# buckler.net
KiCad netlist of a schematic drawn in EAGLE
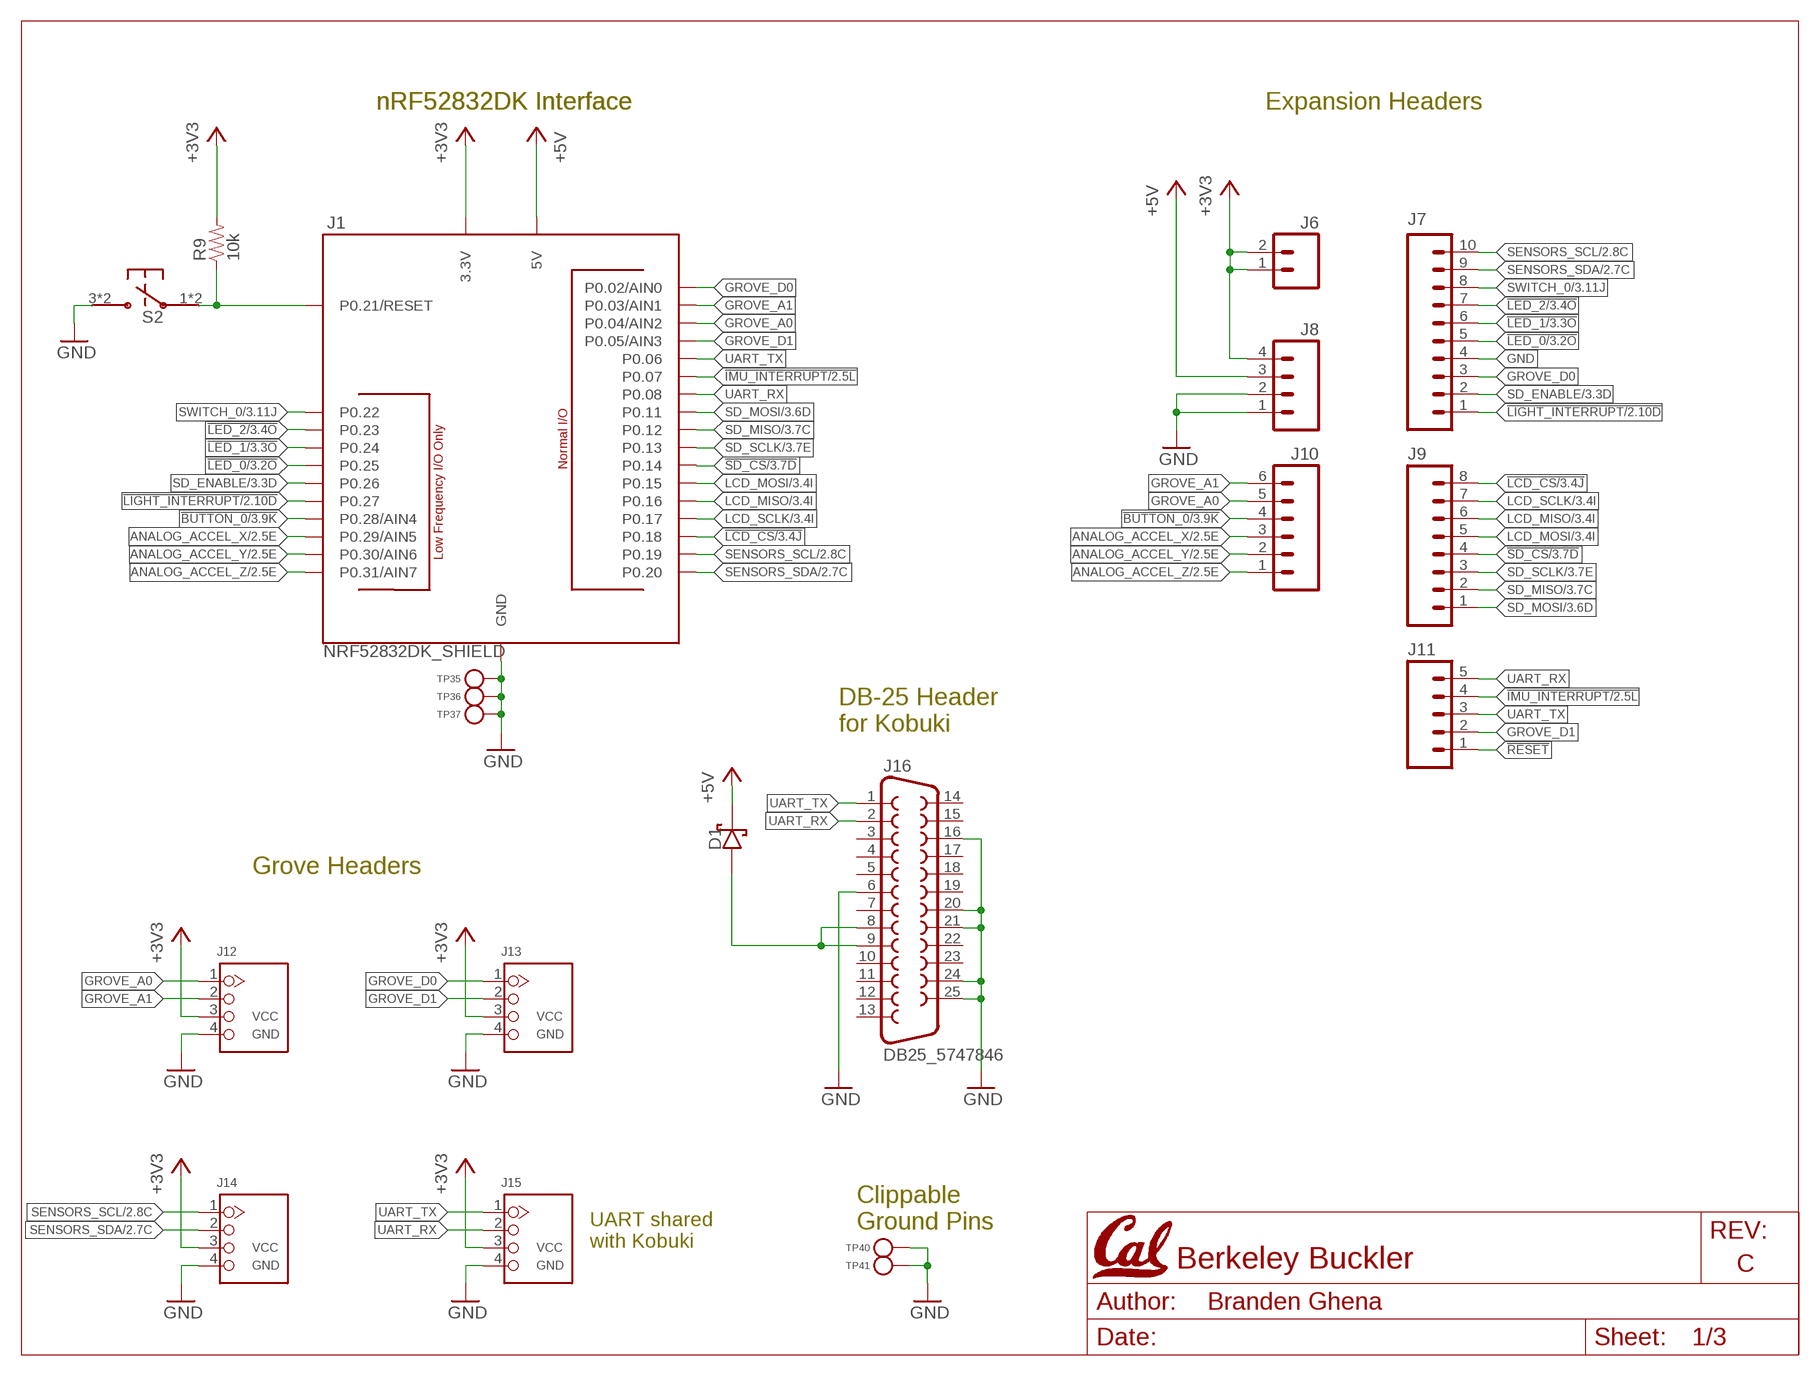
[diagram p0: schematic, sheet 1]
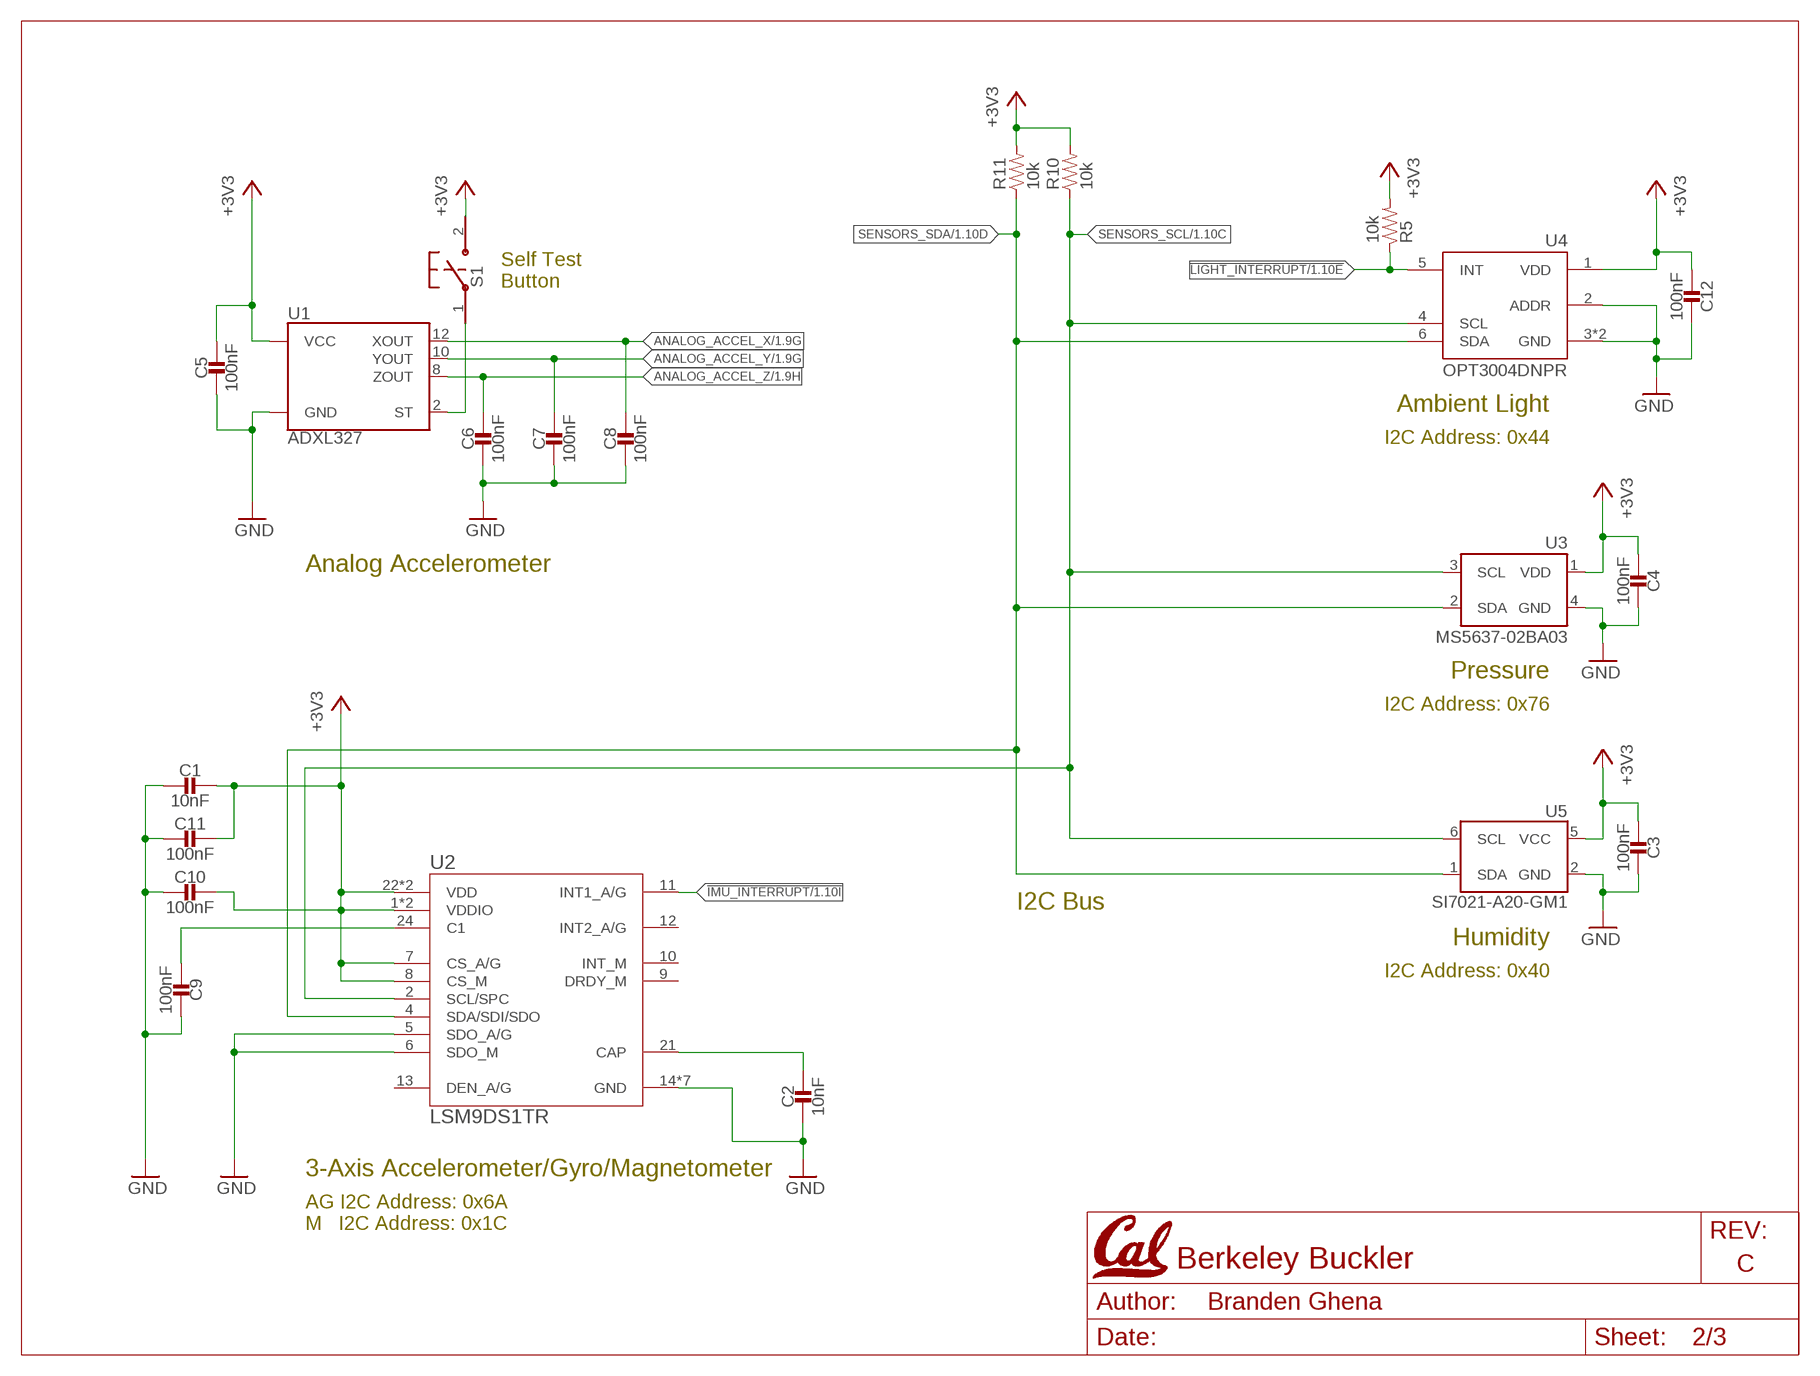
[diagram p1: schematic, sheet 2]
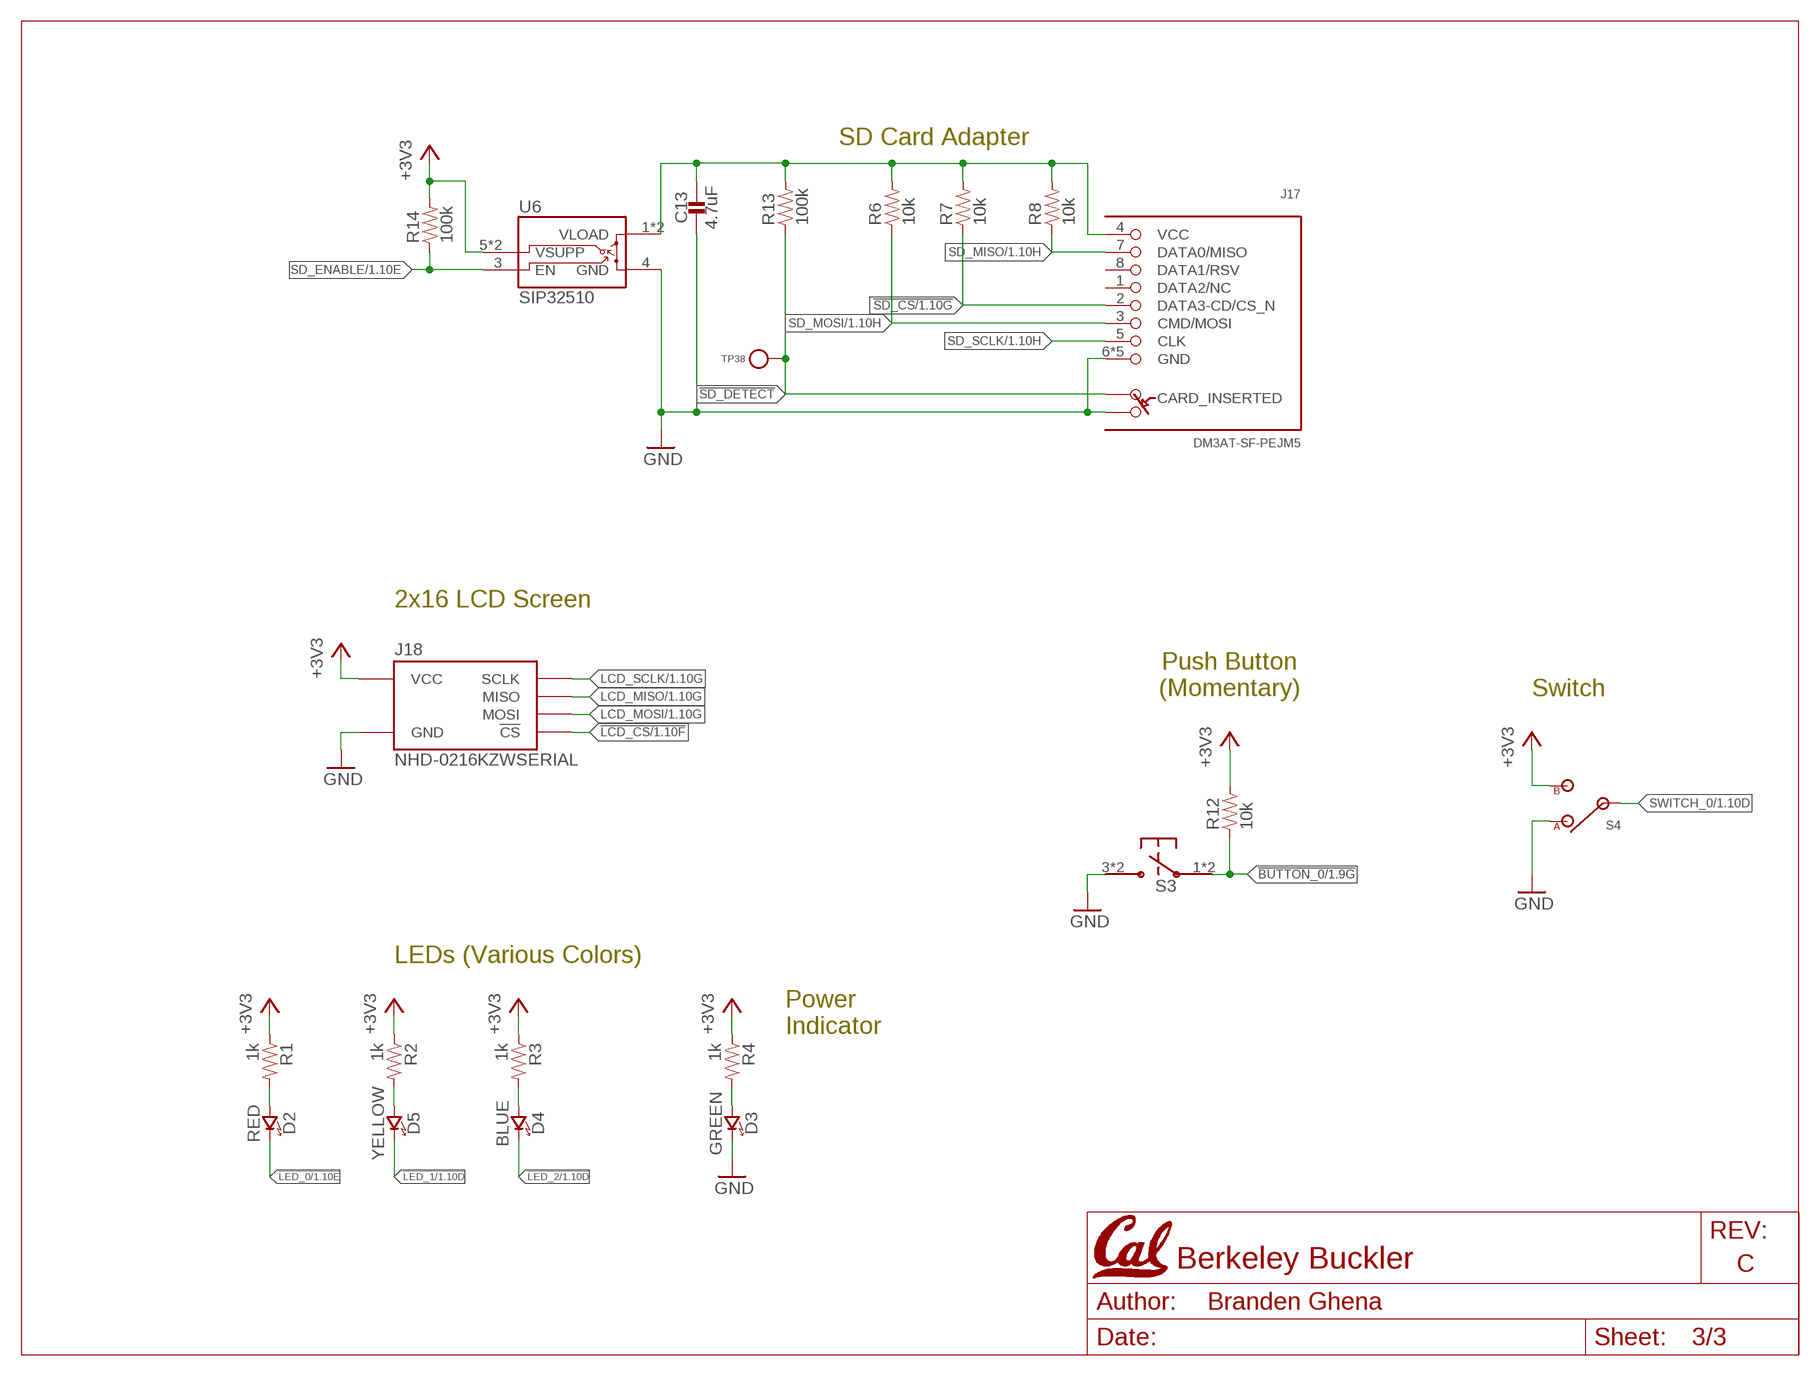
[diagram p2: schematic, sheet 3]

(export (version "E")
  (design (tool "Eeschema 10.0.6"))
  (components
    (comp (ref "D1")
      (value "DIODE_SCHOTTKYSOD323")
      (footprint "eagle-import:SOD323")
      (description "DIODE SCHOTTKY 30V 500MA SOD323")
      (fields (field (name "MANUFACTURER") "Diodes Incorporated") (field (name "MPN") "B0530WS-7-F"))
      (libsource (lib "eagle-import") (part "DIODE_SCHOTTKYSOD323"))
    )
    (comp (ref "J1")
      (value "NRF52832DK_SHIELD")
      (footprint "eagle-import:NRF52832DK_SHIELD")
      (libsource (lib "eagle-import") (part "NRF52832DK_SHIELD"))
    )
    (comp (ref "J6")
      (value "M02PTH")
      (footprint "eagle-import:1X02")
      (libsource (lib "eagle-import") (part "M02PTH"))
    )
    (comp (ref "J7")
      (value "M10\"")
      (footprint "eagle-import:1X10")
      (libsource (lib "eagle-import") (part "M10{dblquote}"))
    )
    (comp (ref "J8")
      (value "M04PTH")
      (footprint "eagle-import:1X04")
      (libsource (lib "eagle-import") (part "M04PTH"))
    )
    (comp (ref "J9")
      (value "M081X08")
      (footprint "eagle-import:1X08")
      (libsource (lib "eagle-import") (part "M081X08"))
    )
    (comp (ref "J10")
      (value "M06SIP")
      (footprint "eagle-import:1X06")
      (libsource (lib "eagle-import") (part "M06SIP"))
    )
    (comp (ref "J11")
      (value "M05PTH")
      (footprint "eagle-import:1X05")
      (libsource (lib "eagle-import") (part "M05PTH"))
    )
    (comp (ref "J12")
      (value "GROVE-CONNECTOR-DIP(4P-2.0)")
      (footprint "eagle-import:HW4-2.0")
      (description "Grove - Universal 4 pin connector")
      (fields (field (name "MANUFACTURER") "Seeed Studio") (field (name "MPN") "110990030"))
      (libsource (lib "eagle-import") (part "GROVE-CONNECTOR-DIP(4P-2.0)"))
    )
    (comp (ref "J13")
      (value "GROVE-CONNECTOR-DIP(4P-2.0)")
      (footprint "eagle-import:HW4-2.0")
      (description "Grove - Universal 4 pin connector")
      (fields (field (name "MANUFACTURER") "Seeed Studio") (field (name "MPN") "110990030"))
      (libsource (lib "eagle-import") (part "GROVE-CONNECTOR-DIP(4P-2.0)"))
    )
    (comp (ref "J14")
      (value "GROVE-CONNECTOR-DIP(4P-2.0)")
      (footprint "eagle-import:HW4-2.0")
      (description "Grove - Universal 4 pin connector")
      (fields (field (name "MANUFACTURER") "Seeed Studio") (field (name "MPN") "110990030"))
      (libsource (lib "eagle-import") (part "GROVE-CONNECTOR-DIP(4P-2.0)"))
    )
    (comp (ref "J15")
      (value "GROVE-CONNECTOR-DIP(4P-2.0)")
      (footprint "eagle-import:HW4-2.0")
      (description "Grove - Universal 4 pin connector")
      (fields (field (name "MANUFACTURER") "Seeed Studio") (field (name "MPN") "110990030"))
      (libsource (lib "eagle-import") (part "GROVE-CONNECTOR-DIP(4P-2.0)"))
    )
    (comp (ref "J16")
      (value "DB25_5747846")
      (footprint "eagle-import:DB25_5747846")
      (description "CONN D-SUB RCPT 25POS R/A SOLDER")
      (fields (field (name "MANUFACTURER") "TE Connectivity AMP Connectors") (field (name "MPN") "5747846-4"))
      (libsource (lib "eagle-import") (part "DB25_5747846"))
    )
    (comp (ref "R9")
      (value "10k")
      (footprint "eagle-import:0402_RES")
      (description "RES SMD 10K OHM 1% 1/16W 0402")
      (fields (field (name "MANUFACTURER") "Samsung Electro-Mechanics") (field (name "MPN") "RC1005F103CS"))
      (libsource (lib "eagle-import") (part "RESISTOR0402_RES"))
    )
    (comp (ref "S2")
      (value "PTS645SM43SMTR92")
      (footprint "eagle-import:PTS645")
      (description "SWITCH TACTILE SPST-NO 0.05A 12V")
      (fields (field (name "MANUFACTURER") "C&K") (field (name "MPN") "PTS645SM43SMTR92 LFS"))
      (libsource (lib "eagle-import") (part "PTS645SM43SMTR92"))
    )
    (comp (ref "TP35")
      (value "TEST_POINT_0.040IN")
      (footprint "eagle-import:TESTPOINT_0.040IN")
      (libsource (lib "eagle-import") (part "TEST_POINT_0.040IN"))
    )
    (comp (ref "TP36")
      (value "TEST_POINT_0.040IN")
      (footprint "eagle-import:TESTPOINT_0.040IN")
      (libsource (lib "eagle-import") (part "TEST_POINT_0.040IN"))
    )
    (comp (ref "TP37")
      (value "TEST_POINT_0.040IN")
      (footprint "eagle-import:TESTPOINT_0.040IN")
      (libsource (lib "eagle-import") (part "TEST_POINT_0.040IN"))
    )
    (comp (ref "TP40")
      (value "TEST_POINT_0.078IN")
      (footprint "eagle-import:TESTPOINT_0.078IN")
      (description "TERM TURRET SINGLE L=4.75MM TIN")
      (fields (field (name "MANUFACTURER") "Keystone Electronics") (field (name "MPN") "1520-2"))
      (libsource (lib "eagle-import") (part "TEST_POINT_0.078IN"))
    )
    (comp (ref "TP41")
      (value "TEST_POINT_0.078IN")
      (footprint "eagle-import:TESTPOINT_0.078IN")
      (description "TERM TURRET SINGLE L=4.75MM TIN")
      (fields (field (name "MANUFACTURER") "Keystone Electronics") (field (name "MPN") "1520-2"))
      (libsource (lib "eagle-import") (part "TEST_POINT_0.078IN"))
    )
    (comp (ref "C1")
      (value "10nF")
      (footprint "eagle-import:0402_CAP")
      (description "CAP CER 10000PF 25V X7R 0402")
      (fields (field (name "MANUFACTURER") "KEMET") (field (name "MPN") "C0402C103J3RACTU"))
      (libsource (lib "eagle-import") (part "CAPACITOR0402_CAP"))
    )
    (comp (ref "C2")
      (value "10nF")
      (footprint "eagle-import:0402_CAP")
      (description "CAP CER 10000PF 25V X7R 0402")
      (fields (field (name "MANUFACTURER") "KEMET") (field (name "MPN") "C0402C103J3RACTU"))
      (libsource (lib "eagle-import") (part "CAPACITOR0402_CAP"))
    )
    (comp (ref "C3")
      (value "100nF")
      (footprint "eagle-import:0402_CAP")
      (description "CAP CER 0.1UF 16V X7R 0402")
      (fields (field (name "MANUFACTURER") "Murata") (field (name "MPN") "GCM155R71C104KA55D"))
      (libsource (lib "eagle-import") (part "CAPACITOR0402_CAP"))
    )
    (comp (ref "C4")
      (value "100nF")
      (footprint "eagle-import:0402_CAP")
      (description "CAP CER 0.1UF 16V X7R 0402")
      (fields (field (name "MANUFACTURER") "Murata") (field (name "MPN") "GCM155R71C104KA55D"))
      (libsource (lib "eagle-import") (part "CAPACITOR0402_CAP"))
    )
    (comp (ref "C5")
      (value "100nF")
      (footprint "eagle-import:0402_CAP")
      (description "CAP CER 0.1UF 16V X7R 0402")
      (fields (field (name "MANUFACTURER") "Murata") (field (name "MPN") "GCM155R71C104KA55D"))
      (libsource (lib "eagle-import") (part "CAPACITOR0402_CAP"))
    )
    (comp (ref "C6")
      (value "100nF")
      (footprint "eagle-import:0402_CAP")
      (description "CAP CER 0.1UF 16V X7R 0402")
      (fields (field (name "MANUFACTURER") "Murata") (field (name "MPN") "GCM155R71C104KA55D"))
      (libsource (lib "eagle-import") (part "CAPACITOR0402_CAP"))
    )
    (comp (ref "C7")
      (value "100nF")
      (footprint "eagle-import:0402_CAP")
      (description "CAP CER 0.1UF 16V X7R 0402")
      (fields (field (name "MANUFACTURER") "Murata") (field (name "MPN") "GCM155R71C104KA55D"))
      (libsource (lib "eagle-import") (part "CAPACITOR0402_CAP"))
    )
    (comp (ref "C8")
      (value "100nF")
      (footprint "eagle-import:0402_CAP")
      (description "CAP CER 0.1UF 16V X7R 0402")
      (fields (field (name "MANUFACTURER") "Murata") (field (name "MPN") "GCM155R71C104KA55D"))
      (libsource (lib "eagle-import") (part "CAPACITOR0402_CAP"))
    )
    (comp (ref "C9")
      (value "100nF")
      (footprint "eagle-import:0402_CAP")
      (description "CAP CER 0.1UF 16V X7R 0402")
      (fields (field (name "MANUFACTURER") "Murata") (field (name "MPN") "GCM155R71C104KA55D"))
      (libsource (lib "eagle-import") (part "CAPACITOR0402_CAP"))
    )
    (comp (ref "C10")
      (value "100nF")
      (footprint "eagle-import:0402_CAP")
      (description "CAP CER 0.1UF 16V X7R 0402")
      (fields (field (name "MANUFACTURER") "Murata") (field (name "MPN") "GCM155R71C104KA55D"))
      (libsource (lib "eagle-import") (part "CAPACITOR0402_CAP"))
    )
    (comp (ref "C11")
      (value "100nF")
      (footprint "eagle-import:0402_CAP")
      (description "CAP CER 0.1UF 16V X7R 0402")
      (fields (field (name "MANUFACTURER") "Murata") (field (name "MPN") "GCM155R71C104KA55D"))
      (libsource (lib "eagle-import") (part "CAPACITOR0402_CAP"))
    )
    (comp (ref "C12")
      (value "100nF")
      (footprint "eagle-import:0402_CAP")
      (description "CAP CER 0.1UF 16V X7R 0402")
      (fields (field (name "MANUFACTURER") "Murata") (field (name "MPN") "GCM155R71C104KA55D"))
      (libsource (lib "eagle-import") (part "CAPACITOR0402_CAP"))
    )
    (comp (ref "R5")
      (value "10k")
      (footprint "eagle-import:0402_RES")
      (description "RES SMD 10K OHM 1% 1/16W 0402")
      (fields (field (name "MANUFACTURER") "Samsung Electro-Mechanics") (field (name "MPN") "RC1005F103CS"))
      (libsource (lib "eagle-import") (part "RESISTOR0402_RES"))
    )
    (comp (ref "R10")
      (value "10k")
      (footprint "eagle-import:0402_RES")
      (description "RES SMD 10K OHM 1% 1/16W 0402")
      (fields (field (name "MANUFACTURER") "Samsung Electro-Mechanics") (field (name "MPN") "RC1005F103CS"))
      (libsource (lib "eagle-import") (part "RESISTOR0402_RES"))
    )
    (comp (ref "R11")
      (value "10k")
      (footprint "eagle-import:0402_RES")
      (description "RES SMD 10K OHM 1% 1/16W 0402")
      (fields (field (name "MANUFACTURER") "Samsung Electro-Mechanics") (field (name "MPN") "RC1005F103CS"))
      (libsource (lib "eagle-import") (part "RESISTOR0402_RES"))
    )
    (comp (ref "S1")
      (value "B3U-1000P")
      (footprint "eagle-import:B3U-1000P")
      (description "SWITCH TACTILE SPST-NO 0.05A 12V")
      (fields (field (name "MANUFACTURER") "Omron") (field (name "MPN") "B3U-1000P"))
      (libsource (lib "eagle-import") (part "B3U-1000P"))
    )
    (comp (ref "U1")
      (value "ADXL327")
      (footprint "eagle-import:LFCSP-16")
      (description "ACCELEROMETER 2G ANALOG 16LFCSP")
      (fields (field (name "MANUFACTURER") "Analog Devices Inc.") (field (name "MPN") "ADXL327BCPZ"))
      (libsource (lib "eagle-import") (part "ADXL327"))
    )
    (comp (ref "U2")
      (value "LSM9DS1TR")
      (footprint "eagle-import:LGA-24_3X3P5X1_STM")
      (fields (field (name "COPYRIGHT") "Copyright (C) 2018 Accelerated Designs. All rights reserved"))
      (libsource (lib "eagle-import") (part "LSM9DS1TR"))
    )
    (comp (ref "U3")
      (value "MS5637-02BA03")
      (footprint "eagle-import:4-SMD")
      (description "SENSOR 17.4PSIA I2C 24B 4-QFN")
      (fields (field (name "MANUFACTURER") "TE CONNECTIVITY") (field (name "MPN") "MS563702BA03-50"))
      (libsource (lib "eagle-import") (part "MS5637-02BA03"))
    )
    (comp (ref "U4")
      (value "OPT3004DNPR")
      (footprint "eagle-import:DNP0006A")
      (fields (field (name "MANUFACTURER") "Texas Instruments"))
      (libsource (lib "eagle-import") (part "OPT3004DNPR"))
    )
    (comp (ref "U5")
      (value "SI7021-A20-GM1")
      (footprint "eagle-import:DFN-6_3MM")
      (description "SENS HUMI/TEMP 3.6V I2C 3% 6DFN")
      (fields (field (name "MANUFACTURER") "Silicon Labs") (field (name "MPN") "SI7021-A20-GM1 "))
      (libsource (lib "eagle-import") (part "SI7021-A20-GM1"))
    )
    (comp (ref "C13")
      (value "4.7uF")
      (footprint "eagle-import:0402_CAP")
      (description "CAP CER 4.7UF 10V X5R 0402")
      (fields
        (field (name "MANUFACTURER") "Samsung Electro-Mechanics")
        (field (name "MPN") "CL05A475KP5NRNC")
      )
      (libsource (lib "eagle-import") (part "CAPACITOR0402_CAP"))
    )
    (comp (ref "D2")
      (value "RED")
      (footprint "eagle-import:LED-0603")
      (description "LED RED CLEAR CHIP SMD")
      (fields (field (name "MANUFACTURER") "Lite-On Inc.") (field (name "MPN") "LTST-C190KRKT"))
      (libsource (lib "eagle-import") (part "LED0603"))
    )
    (comp (ref "D3")
      (value "GREEN")
      (footprint "eagle-import:LED-0603")
      (description "LED GREEN CLEAR CHIP SMD")
      (fields (field (name "MANUFACTURER") "Lite-On Inc.") (field (name "MPN") "LTST-C190KGKT"))
      (libsource (lib "eagle-import") (part "LED0603"))
    )
    (comp (ref "D4")
      (value "BLUE")
      (footprint "eagle-import:LED-0603")
      (description "LED BLUE CLEAR SMD")
      (fields (field (name "MANUFACTURER") "Lite-On Inc.") (field (name "MPN") "LTST-C194TBKT"))
      (libsource (lib "eagle-import") (part "LED0603"))
    )
    (comp (ref "D5")
      (value "YELLOW")
      (footprint "eagle-import:LED-0603")
      (description "LED YELLOW CLEAR CHIP SMD")
      (fields (field (name "MANUFACTURER") "Lite-On Inc.") (field (name "MPN") "LTST-C190KSKT"))
      (libsource (lib "eagle-import") (part "LED0603"))
    )
    (comp (ref "J17")
      (value "DM3AT-SF-PEJM5")
      (footprint "eagle-import:DM3AT-SF-PEJM5")
      (fields (field (name "MANUFACTURER") "Hirose Electric Co Ltd"))
      (libsource (lib "eagle-import") (part "DM3AT-SF-PEJM5"))
    )
    (comp (ref "J18")
      (value "NHD-0216KZWSERIAL")
      (footprint "eagle-import:NHD-0216KZW")
      (libsource (lib "eagle-import") (part "NHD-0216KZWSERIAL"))
    )
    (comp (ref "R1")
      (value "1k")
      (footprint "eagle-import:0402_RES")
      (description "RES SMD 1K OHM 1% 1/16W 0402")
      (fields (field (name "MANUFACTURER") "Stackpole Electronics") (field (name "MPN") "RMCF0402FT1K00"))
      (libsource (lib "eagle-import") (part "RESISTOR0402_RES"))
    )
    (comp (ref "R2")
      (value "1k")
      (footprint "eagle-import:0402_RES")
      (description "RES SMD 1K OHM 1% 1/16W 0402")
      (fields (field (name "MANUFACTURER") "Stackpole Electronics") (field (name "MPN") "RMCF0402FT1K00"))
      (libsource (lib "eagle-import") (part "RESISTOR0402_RES"))
    )
    (comp (ref "R3")
      (value "1k")
      (footprint "eagle-import:0402_RES")
      (description "RES SMD 1K OHM 1% 1/16W 0402")
      (fields (field (name "MANUFACTURER") "Stackpole Electronics") (field (name "MPN") "RMCF0402FT1K00"))
      (libsource (lib "eagle-import") (part "RESISTOR0402_RES"))
    )
    (comp (ref "R4")
      (value "1k")
      (footprint "eagle-import:0402_RES")
      (description "RES SMD 1K OHM 1% 1/16W 0402")
      (fields (field (name "MANUFACTURER") "Stackpole Electronics") (field (name "MPN") "RMCF0402FT1K00"))
      (libsource (lib "eagle-import") (part "RESISTOR0402_RES"))
    )
    (comp (ref "R6")
      (value "10k")
      (footprint "eagle-import:0402_RES")
      (description "RES SMD 10K OHM 1% 1/16W 0402")
      (fields (field (name "MANUFACTURER") "Samsung Electro-Mechanics") (field (name "MPN") "RC1005F103CS"))
      (libsource (lib "eagle-import") (part "RESISTOR0402_RES"))
    )
    (comp (ref "R7")
      (value "10k")
      (footprint "eagle-import:0402_RES")
      (description "RES SMD 10K OHM 1% 1/16W 0402")
      (fields (field (name "MANUFACTURER") "Samsung Electro-Mechanics") (field (name "MPN") "RC1005F103CS"))
      (libsource (lib "eagle-import") (part "RESISTOR0402_RES"))
    )
    (comp (ref "R8")
      (value "10k")
      (footprint "eagle-import:0402_RES")
      (description "RES SMD 10K OHM 1% 1/16W 0402")
      (fields (field (name "MANUFACTURER") "Samsung Electro-Mechanics") (field (name "MPN") "RC1005F103CS"))
      (libsource (lib "eagle-import") (part "RESISTOR0402_RES"))
    )
    (comp (ref "R12")
      (value "10k")
      (footprint "eagle-import:0402_RES")
      (description "RES SMD 10K OHM 1% 1/16W 0402")
      (fields (field (name "MANUFACTURER") "Samsung Electro-Mechanics") (field (name "MPN") "RC1005F103CS"))
      (libsource (lib "eagle-import") (part "RESISTOR0402_RES"))
    )
    (comp (ref "R13")
      (value "100k")
      (footprint "eagle-import:0402_RES")
      (description "RES SMD 100K OHM 1% 1/5W 0402")
      (fields (field (name "MANUFACTURER") "Vishay Dale") (field (name "MPN") "CRCW0402100KFKEDHP"))
      (libsource (lib "eagle-import") (part "RESISTOR0402_RES"))
    )
    (comp (ref "R14")
      (value "100k")
      (footprint "eagle-import:0402_RES")
      (description "RES SMD 100K OHM 1% 1/5W 0402")
      (fields (field (name "MANUFACTURER") "Vishay Dale") (field (name "MPN") "CRCW0402100KFKEDHP"))
      (libsource (lib "eagle-import") (part "RESISTOR0402_RES"))
    )
    (comp (ref "S3")
      (value "PTS645SM43SMTR92")
      (footprint "eagle-import:PTS645")
      (description "SWITCH TACTILE SPST-NO 0.05A 12V")
      (fields (field (name "MANUFACTURER") "C&K") (field (name "MPN") "PTS645SM43SMTR92 LFS"))
      (libsource (lib "eagle-import") (part "PTS645SM43SMTR92"))
    )
    (comp (ref "S4")
      (value "TE_SSA12/SPDT")
      (footprint "eagle-import:TE_SSA12_SPDT")
      (description "SWITCH SLIDE SPDT 100MA 30V")
      (fields
        (field (name "MANUFACTURER") "TE Connectivity ALCOSWITCH Switches")
        (field (name "MPN") "SSA12")
      )
      (libsource (lib "eagle-import") (part "TE_SSA12/SPDT"))
    )
    (comp (ref "TP38")
      (value "TEST_POINT_0.040IN")
      (footprint "eagle-import:TESTPOINT_0.040IN")
      (libsource (lib "eagle-import") (part "TEST_POINT_0.040IN"))
    )
    (comp (ref "U6")
      (value "SIP32510")
      (footprint "eagle-import:TSOT23-6")
      (description "IC LOAD SWITCH SOT23-6")
      (fields (field (name "MANUFACTURER") "Vishay") (field (name "MPN") "SIP32510DT-T1-GE3"))
      (libsource (lib "eagle-import") (part "SIP32510"))
    )
  )
  (nets
    (net (code "1") (name "+3V3") (class "Default")
      (node (ref "C1") (pin "2") (pinfunction "2_2") (pintype "bidirectional"))
      (node (ref "C10") (pin "2") (pinfunction "2_2") (pintype "bidirectional"))
      (node (ref "C11") (pin "2") (pinfunction "2_2") (pintype "bidirectional"))
      (node (ref "C12") (pin "1") (pinfunction "1_1") (pintype "bidirectional"))
      (node (ref "C3") (pin "1") (pinfunction "1_1") (pintype "bidirectional"))
      (node (ref "C4") (pin "1") (pinfunction "1_1") (pintype "bidirectional"))
      (node (ref "C5") (pin "1") (pinfunction "1_1") (pintype "bidirectional"))
      (node (ref "J1") (pin "3.3V@0") (pinfunction "3.3V_3.3V@0") (pintype "bidirectional"))
      (node (ref "J1") (pin "3.3V@1") (pinfunction "3.3V_3.3V@1") (pintype "bidirectional"))
      (node (ref "J1") (pin "3.3V@2") (pinfunction "3.3V_3.3V@2") (pintype "bidirectional"))
      (node (ref "J12") (pin "3") (pinfunction "3_3") (pintype "bidirectional"))
      (node (ref "J13") (pin "3") (pinfunction "3_3") (pintype "bidirectional"))
      (node (ref "J14") (pin "3") (pinfunction "3_3") (pintype "bidirectional"))
      (node (ref "J15") (pin "3") (pinfunction "3_3") (pintype "bidirectional"))
      (node (ref "J18") (pin "2") (pinfunction "VCC_2") (pintype "bidirectional"))
      (node (ref "J6") (pin "1") (pinfunction "1_1") (pintype "passive"))
      (node (ref "J6") (pin "2") (pinfunction "2_2") (pintype "passive"))
      (node (ref "J8") (pin "4") (pinfunction "4_4") (pintype "passive"))
      (node (ref "R1") (pin "1") (pinfunction "1_1") (pintype "passive"))
      (node (ref "R10") (pin "2") (pinfunction "2_2") (pintype "passive"))
      (node (ref "R11") (pin "2") (pinfunction "2_2") (pintype "passive"))
      (node (ref "R12") (pin "2") (pinfunction "2_2") (pintype "passive"))
      (node (ref "R14") (pin "2") (pinfunction "2_2") (pintype "passive"))
      (node (ref "R2") (pin "1") (pinfunction "1_1") (pintype "passive"))
      (node (ref "R3") (pin "1") (pinfunction "1_1") (pintype "passive"))
      (node (ref "R4") (pin "1") (pinfunction "1_1") (pintype "passive"))
      (node (ref "R5") (pin "2") (pinfunction "2_2") (pintype "passive"))
      (node (ref "R9") (pin "2") (pinfunction "2_2") (pintype "passive"))
      (node (ref "S1") (pin "2") (pinfunction "P$2_2") (pintype "passive"))
      (node (ref "S4") (pin "2") (pinfunction "B_2") (pintype "bidirectional"))
      (node (ref "U1") (pin "14") (pinfunction "VCC_14") (pintype "bidirectional"))
      (node (ref "U1") (pin "15") (pinfunction "VCC_15") (pintype "bidirectional"))
      (node (ref "U2") (pin "1") (pinfunction "VDDIO_1") (pintype "power_in"))
      (node (ref "U2") (pin "22") (pinfunction "VDD_22") (pintype "power_in"))
      (node (ref "U2") (pin "23") (pinfunction "VDD_23") (pintype "power_in"))
      (node (ref "U2") (pin "3") (pinfunction "VDDIO_3") (pintype "power_in"))
      (node (ref "U2") (pin "7") (pinfunction "CS_A/G_7") (pintype "bidirectional"))
      (node (ref "U2") (pin "8") (pinfunction "CS_M_8") (pintype "bidirectional"))
      (node (ref "U3") (pin "1") (pinfunction "VDD_1") (pintype "bidirectional"))
      (node (ref "U4") (pin "1") (pinfunction "VDD_1") (pintype "power_in"))
      (node (ref "U5") (pin "5") (pinfunction "VCC_5") (pintype "bidirectional"))
      (node (ref "U6") (pin "5") (pinfunction "VSUPP_5") (pintype "bidirectional"))
      (node (ref "U6") (pin "6") (pinfunction "VSUPP_6") (pintype "bidirectional"))
    )
    (net (code "2") (name "+5V") (class "Default")
      (node (ref "D1") (pin "P$1") (pinfunction "CATHODE_P$1") (pintype "bidirectional"))
      (node (ref "J1") (pin "5V") (pinfunction "5V_5V") (pintype "bidirectional"))
      (node (ref "J8") (pin "3") (pinfunction "3_3") (pintype "passive"))
    )
    (net (code "3") (name "ANALOG_ACCEL_X") (class "Default")
      (node (ref "C8") (pin "1") (pinfunction "1_1") (pintype "bidirectional"))
      (node (ref "J1") (pin "P0.29") (pinfunction "P0.29/AIN5_P0.29") (pintype "bidirectional"))
      (node (ref "J10") (pin "3") (pinfunction "3_3") (pintype "passive"))
      (node (ref "U1") (pin "12") (pinfunction "XOUT_12") (pintype "bidirectional"))
    )
    (net (code "4") (name "ANALOG_ACCEL_Y") (class "Default")
      (node (ref "C7") (pin "1") (pinfunction "1_1") (pintype "bidirectional"))
      (node (ref "J1") (pin "P0.30") (pinfunction "P0.30/AIN6_P0.30") (pintype "bidirectional"))
      (node (ref "J10") (pin "2") (pinfunction "2_2") (pintype "passive"))
      (node (ref "U1") (pin "10") (pinfunction "YOUT_10") (pintype "bidirectional"))
    )
    (net (code "5") (name "ANALOG_ACCEL_Z") (class "Default")
      (node (ref "C6") (pin "1") (pinfunction "1_1") (pintype "bidirectional"))
      (node (ref "J1") (pin "P0.31") (pinfunction "P0.31/AIN7_P0.31") (pintype "bidirectional"))
      (node (ref "J10") (pin "1") (pinfunction "1_1") (pintype "passive"))
      (node (ref "U1") (pin "8") (pinfunction "ZOUT_8") (pintype "bidirectional"))
    )
    (net (code "6") (name "GND") (class "Default")
      (node (ref "C1") (pin "1") (pinfunction "1_1") (pintype "bidirectional"))
      (node (ref "C10") (pin "1") (pinfunction "1_1") (pintype "bidirectional"))
      (node (ref "C11") (pin "1") (pinfunction "1_1") (pintype "bidirectional"))
      (node (ref "C12") (pin "2") (pinfunction "2_2") (pintype "bidirectional"))
      (node (ref "C13") (pin "2") (pinfunction "2_2") (pintype "bidirectional"))
      (node (ref "C2") (pin "1") (pinfunction "1_1") (pintype "bidirectional"))
      (node (ref "C3") (pin "2") (pinfunction "2_2") (pintype "bidirectional"))
      (node (ref "C4") (pin "2") (pinfunction "2_2") (pintype "bidirectional"))
      (node (ref "C5") (pin "2") (pinfunction "2_2") (pintype "bidirectional"))
      (node (ref "C6") (pin "2") (pinfunction "2_2") (pintype "bidirectional"))
      (node (ref "C7") (pin "2") (pinfunction "2_2") (pintype "bidirectional"))
      (node (ref "C8") (pin "2") (pinfunction "2_2") (pintype "bidirectional"))
      (node (ref "C9") (pin "2") (pinfunction "2_2") (pintype "bidirectional"))
      (node (ref "D3") (pin "C") (pinfunction "CATHODE_C") (pintype "bidirectional"))
      (node (ref "J1") (pin "GND@0") (pinfunction "GND_GND@0") (pintype "bidirectional"))
      (node (ref "J1") (pin "GND@1") (pinfunction "GND_GND@1") (pintype "bidirectional"))
      (node (ref "J1") (pin "GND@2") (pinfunction "GND_GND@2") (pintype "bidirectional"))
      (node (ref "J12") (pin "4") (pinfunction "4_4") (pintype "bidirectional"))
      (node (ref "J13") (pin "4") (pinfunction "4_4") (pintype "bidirectional"))
      (node (ref "J14") (pin "4") (pinfunction "4_4") (pintype "bidirectional"))
      (node (ref "J15") (pin "4") (pinfunction "4_4") (pintype "bidirectional"))
      (node (ref "J16") (pin "16") (pinfunction "16_16") (pintype "passive"))
      (node (ref "J16") (pin "20") (pinfunction "20_20") (pintype "passive"))
      (node (ref "J16") (pin "21") (pinfunction "21_21") (pintype "passive"))
      (node (ref "J16") (pin "24") (pinfunction "24_24") (pintype "passive"))
      (node (ref "J16") (pin "25") (pinfunction "25_25") (pintype "passive"))
      (node (ref "J16") (pin "6") (pinfunction "6_6") (pintype "passive"))
      (node (ref "J17") (pin "6") (pinfunction "GND_6") (pintype "bidirectional"))
      (node (ref "J17") (pin "B") (pinfunction "B_B") (pintype "bidirectional"))
      (node (ref "J17") (pin "MOUNT0") (pinfunction "GND_MOUNT0") (pintype "bidirectional"))
      (node (ref "J17") (pin "MOUNT1") (pinfunction "GND_MOUNT1") (pintype "bidirectional"))
      (node (ref "J17") (pin "MOUNT2") (pinfunction "GND_MOUNT2") (pintype "bidirectional"))
      (node (ref "J17") (pin "MOUNT3") (pinfunction "GND_MOUNT3") (pintype "bidirectional"))
      (node (ref "J18") (pin "1") (pinfunction "GND_1") (pintype "bidirectional"))
      (node (ref "J7") (pin "4") (pinfunction "4_4") (pintype "passive"))
      (node (ref "J8") (pin "1") (pinfunction "1_1") (pintype "passive"))
      (node (ref "J8") (pin "2") (pinfunction "2_2") (pintype "passive"))
      (node (ref "S2") (pin "3") (pinfunction "P$2_3") (pintype "passive"))
      (node (ref "S2") (pin "4") (pinfunction "P$2_4") (pintype "passive"))
      (node (ref "S3") (pin "3") (pinfunction "P$2_3") (pintype "passive"))
      (node (ref "S3") (pin "4") (pinfunction "P$2_4") (pintype "passive"))
      (node (ref "S4") (pin "1") (pinfunction "A_1") (pintype "bidirectional"))
      (node (ref "TP35") (pin "TESTPOINT") (pinfunction "TESTPOINT_TESTPOINT") (pintype "bidirectional"))
      (node (ref "TP36") (pin "TESTPOINT") (pinfunction "TESTPOINT_TESTPOINT") (pintype "bidirectional"))
      (node (ref "TP37") (pin "TESTPOINT") (pinfunction "TESTPOINT_TESTPOINT") (pintype "bidirectional"))
      (node (ref "TP40") (pin "1") (pinfunction "TESTPOINT_1") (pintype "bidirectional"))
      (node (ref "TP41") (pin "1") (pinfunction "TESTPOINT_1") (pintype "bidirectional"))
      (node (ref "U1") (pin "3") (pinfunction "GND_3") (pintype "bidirectional"))
      (node (ref "U1") (pin "5") (pinfunction "GND_5") (pintype "bidirectional"))
      (node (ref "U1") (pin "6") (pinfunction "GND_6") (pintype "bidirectional"))
      (node (ref "U1") (pin "7") (pinfunction "GND_7") (pintype "bidirectional"))
      (node (ref "U2") (pin "14") (pinfunction "GND_14") (pintype "power_in"))
      (node (ref "U2") (pin "15") (pinfunction "GND_15") (pintype "power_in"))
      (node (ref "U2") (pin "16") (pinfunction "GND_16") (pintype "power_in"))
      (node (ref "U2") (pin "17") (pinfunction "GND_17") (pintype "power_in"))
      (node (ref "U2") (pin "18") (pinfunction "GND_18") (pintype "power_in"))
      (node (ref "U2") (pin "19") (pinfunction "GND_19") (pintype "power_in"))
      (node (ref "U2") (pin "20") (pinfunction "GND_20") (pintype "power_in"))
      (node (ref "U2") (pin "5") (pinfunction "SDO_A/G_5") (pintype "output"))
      (node (ref "U2") (pin "6") (pinfunction "SDO_M_6") (pintype "output"))
      (node (ref "U3") (pin "4") (pinfunction "GND_4") (pintype "bidirectional"))
      (node (ref "U4") (pin "2") (pinfunction "ADDR_2") (pintype "input"))
      (node (ref "U4") (pin "3") (pinfunction "GND_3") (pintype "power_in"))
      (node (ref "U4") (pin "7") (pinfunction "GND_7") (pintype "power_in"))
      (node (ref "U5") (pin "2") (pinfunction "GND_2") (pintype "bidirectional"))
      (node (ref "U6") (pin "4") (pinfunction "GND_4") (pintype "bidirectional"))
    )
    (net (code "7") (name "GROVE_A0") (class "Default")
      (node (ref "J1") (pin "P0.04") (pinfunction "P0.04/AIN2_P0.04") (pintype "bidirectional"))
      (node (ref "J10") (pin "5") (pinfunction "5_5") (pintype "passive"))
      (node (ref "J12") (pin "1") (pinfunction "1_1") (pintype "bidirectional"))
    )
    (net (code "8") (name "GROVE_A1") (class "Default")
      (node (ref "J1") (pin "P0.03") (pinfunction "P0.03/AIN1_P0.03") (pintype "bidirectional"))
      (node (ref "J10") (pin "6") (pinfunction "6_6") (pintype "passive"))
      (node (ref "J12") (pin "2") (pinfunction "2_2") (pintype "bidirectional"))
    )
    (net (code "9") (name "GROVE_D0") (class "Default")
      (node (ref "J1") (pin "P0.02") (pinfunction "P0.02/AIN0_P0.02") (pintype "bidirectional"))
      (node (ref "J13") (pin "1") (pinfunction "1_1") (pintype "bidirectional"))
      (node (ref "J7") (pin "3") (pinfunction "3_3") (pintype "passive"))
    )
    (net (code "10") (name "GROVE_D1") (class "Default")
      (node (ref "J1") (pin "P0.05") (pinfunction "P0.05/AIN3_P0.05") (pintype "bidirectional"))
      (node (ref "J11") (pin "2") (pinfunction "2_2") (pintype "passive"))
      (node (ref "J13") (pin "2") (pinfunction "2_2") (pintype "bidirectional"))
    )
    (net (code "11") (name "LCD_MISO") (class "Default")
      (node (ref "J1") (pin "P0.16") (pinfunction "P0.16_P0.16") (pintype "bidirectional"))
      (node (ref "J18") (pin "13") (pinfunction "MISO_13") (pintype "bidirectional"))
      (node (ref "J9") (pin "6") (pinfunction "6_6") (pintype "passive"))
    )
    (net (code "12") (name "LCD_MOSI") (class "Default")
      (node (ref "J1") (pin "P0.15") (pinfunction "P0.15_P0.15") (pintype "bidirectional"))
      (node (ref "J18") (pin "14") (pinfunction "MOSI_14") (pintype "bidirectional"))
      (node (ref "J9") (pin "5") (pinfunction "5_5") (pintype "passive"))
    )
    (net (code "13") (name "LCD_SCLK") (class "Default")
      (node (ref "J1") (pin "P0.17") (pinfunction "P0.17_P0.17") (pintype "bidirectional"))
      (node (ref "J18") (pin "12") (pinfunction "SCLK_12") (pintype "bidirectional"))
      (node (ref "J9") (pin "7") (pinfunction "7_7") (pintype "passive"))
    )
    (net (code "14") (name "Net-(D1-ANODE)") (class "Default")
      (node (ref "D1") (pin "P$2") (pinfunction "ANODE_P$2") (pintype "bidirectional"))
      (node (ref "J16") (pin "8") (pinfunction "8_8") (pintype "passive"))
      (node (ref "J16") (pin "9") (pinfunction "9_9") (pintype "passive"))
    )
    (net (code "15") (name "Net-(D2-ANODE)") (class "Default")
      (node (ref "D2") (pin "A") (pinfunction "ANODE_A") (pintype "bidirectional"))
      (node (ref "R1") (pin "2") (pinfunction "2_2") (pintype "passive"))
    )
    (net (code "16") (name "Net-(D3-ANODE)") (class "Default")
      (node (ref "D3") (pin "A") (pinfunction "ANODE_A") (pintype "bidirectional"))
      (node (ref "R4") (pin "2") (pinfunction "2_2") (pintype "passive"))
    )
    (net (code "17") (name "Net-(D4-ANODE)") (class "Default")
      (node (ref "D4") (pin "A") (pinfunction "ANODE_A") (pintype "bidirectional"))
      (node (ref "R3") (pin "2") (pinfunction "2_2") (pintype "passive"))
    )
    (net (code "18") (name "Net-(D5-ANODE)") (class "Default")
      (node (ref "D5") (pin "A") (pinfunction "ANODE_A") (pintype "bidirectional"))
      (node (ref "R2") (pin "2") (pinfunction "2_2") (pintype "passive"))
    )
    (net (code "19") (name "Net-(J17-VCC)") (class "Default")
      (node (ref "C13") (pin "1") (pinfunction "1_1") (pintype "bidirectional"))
      (node (ref "J17") (pin "4") (pinfunction "VCC_4") (pintype "bidirectional"))
      (node (ref "R13") (pin "2") (pinfunction "2_2") (pintype "passive"))
      (node (ref "R6") (pin "2") (pinfunction "2_2") (pintype "passive"))
      (node (ref "R7") (pin "2") (pinfunction "2_2") (pintype "passive"))
      (node (ref "R8") (pin "2") (pinfunction "2_2") (pintype "passive"))
      (node (ref "U6") (pin "1") (pinfunction "VLOAD_1") (pintype "bidirectional"))
      (node (ref "U6") (pin "2") (pinfunction "VLOAD_2") (pintype "bidirectional"))
    )
    (net (code "20") (name "Net-(S1-P$1)") (class "Default")
      (node (ref "S1") (pin "1") (pinfunction "P$1_1") (pintype "passive"))
      (node (ref "U1") (pin "2") (pinfunction "ST_2") (pintype "bidirectional"))
    )
    (net (code "21") (name "Net-(U2-C1)") (class "Default")
      (node (ref "C9") (pin "1") (pinfunction "1_1") (pintype "bidirectional"))
      (node (ref "U2") (pin "24") (pinfunction "C1_24") (pintype "bidirectional"))
    )
    (net (code "22") (name "Net-(U2-CAP)") (class "Default")
      (node (ref "C2") (pin "2") (pinfunction "2_2") (pintype "bidirectional"))
      (node (ref "U2") (pin "21") (pinfunction "CAP_21") (pintype "passive"))
    )
    (net (code "23") (name "SD_ENABLE") (class "Default")
      (node (ref "J1") (pin "P0.26") (pinfunction "P0.26_P0.26") (pintype "bidirectional"))
      (node (ref "J7") (pin "2") (pinfunction "2_2") (pintype "passive"))
      (node (ref "R14") (pin "1") (pinfunction "1_1") (pintype "passive"))
      (node (ref "U6") (pin "3") (pinfunction "EN_3") (pintype "bidirectional"))
    )
    (net (code "24") (name "SD_MISO") (class "Default")
      (node (ref "J1") (pin "P0.12") (pinfunction "P0.12_P0.12") (pintype "bidirectional"))
      (node (ref "J17") (pin "7") (pinfunction "DATA0/MISO_7") (pintype "bidirectional"))
      (node (ref "J9") (pin "2") (pinfunction "2_2") (pintype "passive"))
      (node (ref "R8") (pin "1") (pinfunction "1_1") (pintype "passive"))
    )
    (net (code "25") (name "SD_MOSI") (class "Default")
      (node (ref "J1") (pin "P0.11") (pinfunction "P0.11_P0.11") (pintype "bidirectional"))
      (node (ref "J17") (pin "3") (pinfunction "CMD/MOSI_3") (pintype "bidirectional"))
      (node (ref "J9") (pin "1") (pinfunction "1_1") (pintype "passive"))
      (node (ref "R6") (pin "1") (pinfunction "1_1") (pintype "passive"))
    )
    (net (code "26") (name "SD_SCLK") (class "Default")
      (node (ref "J1") (pin "P0.13") (pinfunction "P0.13_P0.13") (pintype "bidirectional"))
      (node (ref "J17") (pin "5") (pinfunction "CLK_5") (pintype "bidirectional"))
      (node (ref "J9") (pin "3") (pinfunction "3_3") (pintype "passive"))
    )
    (net (code "27") (name "SENSORS_SCL") (class "Default")
      (node (ref "J1") (pin "P0.19") (pinfunction "P0.19_P0.19") (pintype "bidirectional"))
      (node (ref "J14") (pin "1") (pinfunction "1_1") (pintype "bidirectional"))
      (node (ref "J7") (pin "10") (pinfunction "10_10") (pintype "passive"))
      (node (ref "R10") (pin "1") (pinfunction "1_1") (pintype "passive"))
      (node (ref "U2") (pin "2") (pinfunction "SCL/SPC_2") (pintype "bidirectional"))
      (node (ref "U3") (pin "3") (pinfunction "SCL_3") (pintype "bidirectional"))
      (node (ref "U4") (pin "4") (pinfunction "SCL_4") (pintype "input"))
      (node (ref "U5") (pin "6") (pinfunction "SCL_6") (pintype "bidirectional"))
    )
    (net (code "28") (name "SENSORS_SDA") (class "Default")
      (node (ref "J1") (pin "P0.20") (pinfunction "P0.20_P0.20") (pintype "bidirectional"))
      (node (ref "J14") (pin "2") (pinfunction "2_2") (pintype "bidirectional"))
      (node (ref "J7") (pin "9") (pinfunction "9_9") (pintype "passive"))
      (node (ref "R11") (pin "1") (pinfunction "1_1") (pintype "passive"))
      (node (ref "U2") (pin "4") (pinfunction "SDA/SDI/SDO_4") (pintype "bidirectional"))
      (node (ref "U3") (pin "2") (pinfunction "SDA_2") (pintype "bidirectional"))
      (node (ref "U4") (pin "6") (pinfunction "SDA_6") (pintype "input"))
      (node (ref "U5") (pin "1") (pinfunction "SDA_1") (pintype "bidirectional"))
    )
    (net (code "29") (name "SWITCH_0") (class "Default")
      (node (ref "J1") (pin "P0.22") (pinfunction "P0.22_P0.22") (pintype "bidirectional"))
      (node (ref "J7") (pin "8") (pinfunction "8_8") (pintype "passive"))
      (node (ref "S4") (pin "IN") (pinfunction "IN_IN") (pintype "bidirectional"))
    )
    (net (code "30") (name "UART_RX") (class "Default")
      (node (ref "J1") (pin "P0.08") (pinfunction "P0.08_P0.08") (pintype "bidirectional"))
      (node (ref "J11") (pin "5") (pinfunction "5_5") (pintype "passive"))
      (node (ref "J15") (pin "2") (pinfunction "2_2") (pintype "bidirectional"))
      (node (ref "J16") (pin "2") (pinfunction "2_2") (pintype "passive"))
    )
    (net (code "31") (name "UART_TX") (class "Default")
      (node (ref "J1") (pin "P0.06") (pinfunction "P0.06_P0.06") (pintype "bidirectional"))
      (node (ref "J11") (pin "3") (pinfunction "3_3") (pintype "passive"))
      (node (ref "J15") (pin "1") (pinfunction "1_1") (pintype "bidirectional"))
      (node (ref "J16") (pin "1") (pinfunction "1_1") (pintype "passive"))
    )
    (net (code "32") (name "unconnected-(J16-Pad3)") (class "Default")
      (node (ref "J16") (pin "3") (pinfunction "3_3") (pintype "passive"))
    )
    (net (code "33") (name "unconnected-(J16-Pad4)") (class "Default")
      (node (ref "J16") (pin "4") (pinfunction "4_4") (pintype "passive"))
    )
    (net (code "34") (name "unconnected-(J16-Pad5)") (class "Default")
      (node (ref "J16") (pin "5") (pinfunction "5_5") (pintype "passive"))
    )
    (net (code "35") (name "unconnected-(J16-Pad7)") (class "Default")
      (node (ref "J16") (pin "7") (pinfunction "7_7") (pintype "passive"))
    )
    (net (code "36") (name "unconnected-(J16-Pad10)") (class "Default")
      (node (ref "J16") (pin "10") (pinfunction "10_10") (pintype "passive"))
    )
    (net (code "37") (name "unconnected-(J16-Pad11)") (class "Default")
      (node (ref "J16") (pin "11") (pinfunction "11_11") (pintype "passive"))
    )
    (net (code "38") (name "unconnected-(J16-Pad12)") (class "Default")
      (node (ref "J16") (pin "12") (pinfunction "12_12") (pintype "passive"))
    )
    (net (code "39") (name "unconnected-(J16-Pad13)") (class "Default")
      (node (ref "J16") (pin "13") (pinfunction "13_13") (pintype "passive"))
    )
    (net (code "40") (name "unconnected-(J16-Pad14)") (class "Default")
      (node (ref "J16") (pin "14") (pinfunction "14_14") (pintype "passive"))
    )
    (net (code "41") (name "unconnected-(J16-Pad15)") (class "Default")
      (node (ref "J16") (pin "15") (pinfunction "15_15") (pintype "passive"))
    )
    (net (code "42") (name "unconnected-(J16-Pad17)") (class "Default")
      (node (ref "J16") (pin "17") (pinfunction "17_17") (pintype "passive"))
    )
    (net (code "43") (name "unconnected-(J16-Pad18)") (class "Default")
      (node (ref "J16") (pin "18") (pinfunction "18_18") (pintype "passive"))
    )
    (net (code "44") (name "unconnected-(J16-Pad19)") (class "Default")
      (node (ref "J16") (pin "19") (pinfunction "19_19") (pintype "passive"))
    )
    (net (code "45") (name "unconnected-(J16-Pad22)") (class "Default")
      (node (ref "J16") (pin "22") (pinfunction "22_22") (pintype "passive"))
    )
    (net (code "46") (name "unconnected-(J16-Pad23)") (class "Default")
      (node (ref "J16") (pin "23") (pinfunction "23_23") (pintype "passive"))
    )
    (net (code "47") (name "unconnected-(J17-DATA1{slash}RSV-Pad8)") (class "Default")
      (node (ref "J17") (pin "8") (pinfunction "DATA1/RSV_8") (pintype "bidirectional"))
    )
    (net (code "48") (name "unconnected-(J17-DATA2{slash}NC-Pad1)") (class "Default")
      (node (ref "J17") (pin "1") (pinfunction "DATA2/NC_1") (pintype "bidirectional"))
    )
    (net (code "49") (name "unconnected-(U2-DEN_A{slash}G-Pad13)") (class "Default")
      (node (ref "U2") (pin "13") (pinfunction "DEN_A/G_13") (pintype "bidirectional"))
    )
    (net (code "50") (name "unconnected-(U2-DRDY_M-Pad9)") (class "Default")
      (node (ref "U2") (pin "9") (pinfunction "DRDY_M_9") (pintype "bidirectional"))
    )
    (net (code "51") (name "unconnected-(U2-INT2_A{slash}G-Pad12)") (class "Default")
      (node (ref "U2") (pin "12") (pinfunction "INT2_A/G_12") (pintype "bidirectional"))
    )
    (net (code "52") (name "unconnected-(U2-INT_M-Pad10)") (class "Default")
      (node (ref "U2") (pin "10") (pinfunction "INT_M_10") (pintype "bidirectional"))
    )
    (net (code "53") (name "~{BUTTON_0}") (class "Default")
      (node (ref "J1") (pin "P0.28") (pinfunction "P0.28/AIN4_P0.28") (pintype "bidirectional"))
      (node (ref "J10") (pin "4") (pinfunction "4_4") (pintype "passive"))
      (node (ref "R12") (pin "1") (pinfunction "1_1") (pintype "passive"))
      (node (ref "S3") (pin "1") (pinfunction "P$1_1") (pintype "passive"))
      (node (ref "S3") (pin "2") (pinfunction "P$1_2") (pintype "passive"))
    )
    (net (code "54") (name "~{IMU_INTERRUPT}") (class "Default")
      (node (ref "J1") (pin "P0.07") (pinfunction "P0.07_P0.07") (pintype "bidirectional"))
      (node (ref "J11") (pin "4") (pinfunction "4_4") (pintype "passive"))
      (node (ref "U2") (pin "11") (pinfunction "INT1_A/G_11") (pintype "bidirectional"))
    )
    (net (code "55") (name "~{LCD_CS}") (class "Default")
      (node (ref "J1") (pin "P0.18") (pinfunction "P0.18_P0.18") (pintype "bidirectional"))
      (node (ref "J18") (pin "16") (pinfunction "~{CS}_16") (pintype "bidirectional"))
      (node (ref "J9") (pin "8") (pinfunction "8_8") (pintype "passive"))
    )
    (net (code "56") (name "~{LED_0}") (class "Default")
      (node (ref "D2") (pin "C") (pinfunction "CATHODE_C") (pintype "bidirectional"))
      (node (ref "J1") (pin "P0.25") (pinfunction "P0.25_P0.25") (pintype "bidirectional"))
      (node (ref "J7") (pin "5") (pinfunction "5_5") (pintype "passive"))
    )
    (net (code "57") (name "~{LED_1}") (class "Default")
      (node (ref "D5") (pin "C") (pinfunction "CATHODE_C") (pintype "bidirectional"))
      (node (ref "J1") (pin "P0.24") (pinfunction "P0.24_P0.24") (pintype "bidirectional"))
      (node (ref "J7") (pin "6") (pinfunction "6_6") (pintype "passive"))
    )
    (net (code "58") (name "~{LED_2}") (class "Default")
      (node (ref "D4") (pin "C") (pinfunction "CATHODE_C") (pintype "bidirectional"))
      (node (ref "J1") (pin "P0.23") (pinfunction "P0.23_P0.23") (pintype "bidirectional"))
      (node (ref "J7") (pin "7") (pinfunction "7_7") (pintype "passive"))
    )
    (net (code "59") (name "~{LIGHT_INTERRUPT}") (class "Default")
      (node (ref "J1") (pin "P0.27") (pinfunction "P0.27_P0.27") (pintype "bidirectional"))
      (node (ref "J7") (pin "1") (pinfunction "1_1") (pintype "passive"))
      (node (ref "R5") (pin "1") (pinfunction "1_1") (pintype "passive"))
      (node (ref "U4") (pin "5") (pinfunction "INT_5") (pintype "output"))
    )
    (net (code "60") (name "~{RESET}") (class "Default")
      (node (ref "J1") (pin "P0.21") (pinfunction "P0.21/RESET_P0.21") (pintype "bidirectional"))
      (node (ref "J11") (pin "1") (pinfunction "1_1") (pintype "passive"))
      (node (ref "R9") (pin "1") (pinfunction "1_1") (pintype "passive"))
      (node (ref "S2") (pin "1") (pinfunction "P$1_1") (pintype "passive"))
      (node (ref "S2") (pin "2") (pinfunction "P$1_2") (pintype "passive"))
    )
    (net (code "61") (name "~{SD_CS}") (class "Default")
      (node (ref "J1") (pin "P0.14") (pinfunction "P0.14_P0.14") (pintype "bidirectional"))
      (node (ref "J17") (pin "2") (pinfunction "DATA3-CD/CS_N_2") (pintype "bidirectional"))
      (node (ref "J9") (pin "4") (pinfunction "4_4") (pintype "passive"))
      (node (ref "R7") (pin "1") (pinfunction "1_1") (pintype "passive"))
    )
    (net (code "62") (name "~{SD_DETECT}") (class "Default")
      (node (ref "J17") (pin "A") (pinfunction "A_A") (pintype "bidirectional"))
      (node (ref "R13") (pin "1") (pinfunction "1_1") (pintype "passive"))
      (node (ref "TP38") (pin "TESTPOINT") (pinfunction "TESTPOINT_TESTPOINT") (pintype "bidirectional"))
    )
  )
)
